# Power.net
KiCad netlist of a schematic drawn in Altium Designer
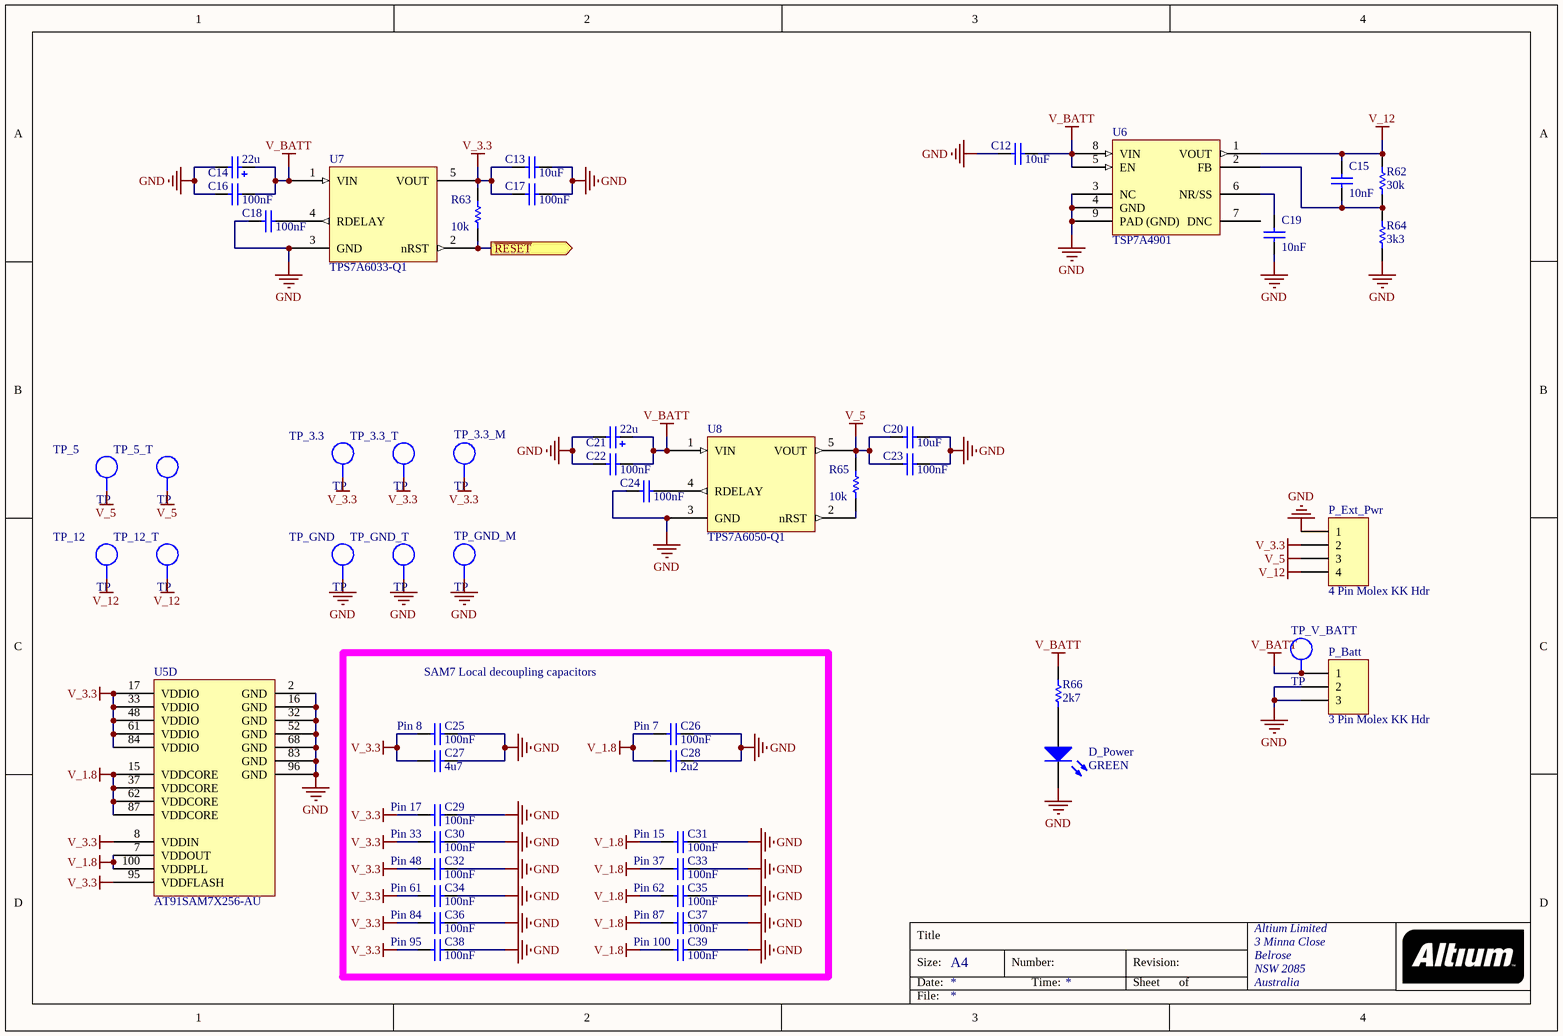
[diagram p0: Power.SchDoc]

(export (version "E")
  (design (tool "Eeschema 10.0.6"))
  (components
    (comp (ref "C12")
      (value "10uF")
      (footprint "0805")
      (description "CAP 10uF 10% 10V X5R 0805")
      (fields (field (name "MANUFACTURER") "Murata") (field (name "PART NUMBER") "CP_10uF 0805"))
      (libsource (lib "ENEL429_4") (part "CP_10uF 0805"))
    )
    (comp (ref "C13")
      (value "10uF")
      (footprint "0805")
      (description "CAP 10uF 10% 10V X5R 0805")
      (fields (field (name "PART NUMBER") "CP_10uF 0805") (field (name "MANUFACTURER") "Murata"))
      (libsource (lib "ENEL429_4") (part "CP_10uF 0805"))
    )
    (comp (ref "C14")
      (value "22u")
      (footprint "6032")
      (description "CAP TANT 22UF 35V 10% SMD")
      (fields (field (name "MANUFACTURER") "Vishay") (field (name "PART NUMBER") "CP_TANT_22uF_35V"))
      (libsource (lib "ENEL429_4") (part "CP_TANT_22uF_35V"))
    )
    (comp (ref "C15")
      (value "10nF")
      (footprint "0603")
      (description "CAP CER 10000PF 100V X7R 0603")
      (fields (field (name "MANUFACTURER") "Taiyo Yuden") (field (name "PART NUMBER") "CP_10nF 0603"))
      (libsource (lib "ENEL429_4") (part "CP_10nF 0603"))
    )
    (comp (ref "C16")
      (value "100nF")
      (footprint "0603")
      (description "CAP CER .10UF 50V X5R 0603")
      (fields (field (name "PART NUMBER") "CP_100nF 0603") (field (name "MANUFACTURER") "Taiyo Yuden"))
      (libsource (lib "ENEL429_4") (part "CP_100nF 0603"))
    )
    (comp (ref "C17")
      (value "100nF")
      (footprint "0603")
      (description "CAP CER .10UF 50V X5R 0603")
      (fields (field (name "PART NUMBER") "CP_100nF 0603") (field (name "MANUFACTURER") "Taiyo Yuden"))
      (libsource (lib "ENEL429_4") (part "CP_100nF 0603"))
    )
    (comp (ref "C18")
      (value "100nF")
      (footprint "0603")
      (description "CAP CER .10UF 50V X5R 0603")
      (fields (field (name "MANUFACTURER") "Taiyo Yuden") (field (name "PART NUMBER") "CP_100nF 0603"))
      (libsource (lib "ENEL429_4") (part "CP_100nF 0603"))
    )
    (comp (ref "C19")
      (value "10nF")
      (footprint "0603")
      (description "CAP CER 10000PF 100V X7R 0603")
      (fields (field (name "MANUFACTURER") "Taiyo Yuden") (field (name "PART NUMBER") "CP_10nF 0603"))
      (libsource (lib "ENEL429_4") (part "CP_10nF 0603"))
    )
    (comp (ref "C20")
      (value "10uF")
      (footprint "0805")
      (description "CAP 10uF 10% 10V X5R 0805")
      (fields (field (name "PART NUMBER") "CP_10uF 0805") (field (name "MANUFACTURER") "Murata"))
      (libsource (lib "ENEL429_4") (part "CP_10uF 0805"))
    )
    (comp (ref "C21")
      (value "22u")
      (footprint "6032")
      (description "CAP TANT 22UF 35V 10% SMD")
      (fields (field (name "MANUFACTURER") "Vishay") (field (name "PART NUMBER") "CP_TANT_22uF_35V"))
      (libsource (lib "ENEL429_4") (part "CP_TANT_22uF_35V"))
    )
    (comp (ref "C22")
      (value "100nF")
      (footprint "0603")
      (description "CAP CER .10UF 50V X5R 0603")
      (fields (field (name "PART NUMBER") "CP_100nF 0603") (field (name "MANUFACTURER") "Taiyo Yuden"))
      (libsource (lib "ENEL429_4") (part "CP_100nF 0603"))
    )
    (comp (ref "C23")
      (value "100nF")
      (footprint "0603")
      (description "CAP CER .10UF 50V X5R 0603")
      (fields (field (name "PART NUMBER") "CP_100nF 0603") (field (name "MANUFACTURER") "Taiyo Yuden"))
      (libsource (lib "ENEL429_4") (part "CP_100nF 0603"))
    )
    (comp (ref "C24")
      (value "100nF")
      (footprint "0603")
      (description "CAP CER .10UF 50V X5R 0603")
      (fields (field (name "MANUFACTURER") "Taiyo Yuden") (field (name "PART NUMBER") "CP_100nF 0603"))
      (libsource (lib "ENEL429_4") (part "CP_100nF 0603"))
    )
    (comp (ref "C25")
      (value "100nF")
      (footprint "0603")
      (description "CAP CER .10UF 50V X5R 0603")
      (fields (field (name "PART NUMBER") "CP_100nF 0603") (field (name "MANUFACTURER") "Taiyo Yuden"))
      (libsource (lib "ENEL429_4") (part "CP_100nF 0603"))
    )
    (comp (ref "C26")
      (value "100nF")
      (footprint "0603")
      (description "CAP CER .10UF 50V X5R 0603")
      (fields (field (name "PART NUMBER") "CP_100nF 0603") (field (name "MANUFACTURER") "Taiyo Yuden"))
      (libsource (lib "ENEL429_4") (part "CP_100nF 0603"))
    )
    (comp (ref "C27")
      (value "4u7")
      (footprint "0603")
      (description "CAP CER 4.7UF 10V X5R 0603")
      (fields
        (field (name "PART NUMBER") "CP_4u7 0603")
        (field (name "MANUFACTURER") "Taiyo Yuden LMK107BJ475KA-T")
      )
      (libsource (lib "ENEL429_4") (part "CP_4u7 0603"))
    )
    (comp (ref "C28")
      (value "2u2")
      (footprint "0603")
      (description "CAP CER 2.2UF 10V 10% X5R 0603")
      (fields
        (field (name "PART NUMBER") "CP_2u2F_10V_0603")
        (field (name "MANUFACTURER") "Murata Electronics North America")
        (field (name "VERIFY") "not verified")
      )
      (libsource (lib "ENEL429_4") (part "CP_2u2F_10V_0603"))
    )
    (comp (ref "C29")
      (value "100nF")
      (footprint "0603")
      (description "CAP CER .10UF 50V X5R 0603")
      (fields (field (name "PART NUMBER") "CP_100nF 0603") (field (name "MANUFACTURER") "Taiyo Yuden"))
      (libsource (lib "ENEL429_4") (part "CP_100nF 0603"))
    )
    (comp (ref "C30")
      (value "100nF")
      (footprint "0603")
      (description "CAP CER .10UF 50V X5R 0603")
      (fields (field (name "PART NUMBER") "CP_100nF 0603") (field (name "MANUFACTURER") "Taiyo Yuden"))
      (libsource (lib "ENEL429_4") (part "CP_100nF 0603"))
    )
    (comp (ref "C31")
      (value "100nF")
      (footprint "0603")
      (description "CAP CER .10UF 50V X5R 0603")
      (fields (field (name "PART NUMBER") "CP_100nF 0603") (field (name "MANUFACTURER") "Taiyo Yuden"))
      (libsource (lib "ENEL429_4") (part "CP_100nF 0603"))
    )
    (comp (ref "C32")
      (value "100nF")
      (footprint "0603")
      (description "CAP CER .10UF 50V X5R 0603")
      (fields (field (name "PART NUMBER") "CP_100nF 0603") (field (name "MANUFACTURER") "Taiyo Yuden"))
      (libsource (lib "ENEL429_4") (part "CP_100nF 0603"))
    )
    (comp (ref "C33")
      (value "100nF")
      (footprint "0603")
      (description "CAP CER .10UF 50V X5R 0603")
      (fields (field (name "PART NUMBER") "CP_100nF 0603") (field (name "MANUFACTURER") "Taiyo Yuden"))
      (libsource (lib "ENEL429_4") (part "CP_100nF 0603"))
    )
    (comp (ref "C34")
      (value "100nF")
      (footprint "0603")
      (description "CAP CER .10UF 50V X5R 0603")
      (fields (field (name "PART NUMBER") "CP_100nF 0603") (field (name "MANUFACTURER") "Taiyo Yuden"))
      (libsource (lib "ENEL429_4") (part "CP_100nF 0603"))
    )
    (comp (ref "C35")
      (value "100nF")
      (footprint "0603")
      (description "CAP CER .10UF 50V X5R 0603")
      (fields (field (name "PART NUMBER") "CP_100nF 0603") (field (name "MANUFACTURER") "Taiyo Yuden"))
      (libsource (lib "ENEL429_4") (part "CP_100nF 0603"))
    )
    (comp (ref "C36")
      (value "100nF")
      (footprint "0603")
      (description "CAP CER .10UF 50V X5R 0603")
      (fields (field (name "PART NUMBER") "CP_100nF 0603") (field (name "MANUFACTURER") "Taiyo Yuden"))
      (libsource (lib "ENEL429_4") (part "CP_100nF 0603"))
    )
    (comp (ref "C37")
      (value "100nF")
      (footprint "0603")
      (description "CAP CER .10UF 50V X5R 0603")
      (fields (field (name "PART NUMBER") "CP_100nF 0603") (field (name "MANUFACTURER") "Taiyo Yuden"))
      (libsource (lib "ENEL429_4") (part "CP_100nF 0603"))
    )
    (comp (ref "C38")
      (value "100nF")
      (footprint "0603")
      (description "CAP CER .10UF 50V X5R 0603")
      (fields (field (name "PART NUMBER") "CP_100nF 0603") (field (name "MANUFACTURER") "Taiyo Yuden"))
      (libsource (lib "ENEL429_4") (part "CP_100nF 0603"))
    )
    (comp (ref "C39")
      (value "100nF")
      (footprint "0603")
      (description "CAP CER .10UF 50V X5R 0603")
      (fields (field (name "PART NUMBER") "CP_100nF 0603") (field (name "MANUFACTURER") "Taiyo Yuden"))
      (libsource (lib "ENEL429_4") (part "CP_100nF 0603"))
    )
    (comp (ref "D_Power")
      (value "GREEN")
      (footprint "DIODE_0805")
      (description "Green LED 0805")
      (fields (field (name "MANUFACTURER") "Vishay") (field (name "PART NUMBER") "DL_LED Green 0805"))
      (libsource (lib "ENEL429_4") (part "DL_LED Green 0805"))
    )
    (comp (ref "P_Batt")
      (value "3 Pin Molex KK Hdr")
      (footprint "G_MOLEX_KK_3_HDR")
      (description "CONN HEADER 3POS .100 VERT TIN")
      (fields (field (name "MANUFACTURER") "Molex/Waldom") (field (name "PART NUMBER") "JP_MOLEX_KK_3POS"))
      (libsource (lib "ENEL429_4") (part "JP_MOLEX_KK_3POS"))
    )
    (comp (ref "P_Ext_Pwr")
      (value "4 Pin Molex KK Hdr")
      (footprint "G_MOLEX_KK_4_HDR")
      (description "CONN HEADER 4POS .100 VERT TIN")
      (fields (field (name "MANUFACTURER") "Molex/Waldom") (field (name "PART NUMBER") "JP_MOLEX_KK_4POS"))
      (libsource (lib "ENEL429_4") (part "JP_MOLEX_KK_4POS"))
    )
    (comp (ref "R62")
      (value "30k")
      (footprint "0603")
      (description "RES 30K OHM 1/10W 1% 0603 SMD")
      (fields (field (name "MANUFACTURER") "Yageo") (field (name "PART NUMBER") "RS_30k 0603"))
      (libsource (lib "ENEL429_4") (part "RS_30k 0603"))
    )
    (comp (ref "R63")
      (value "10k")
      (footprint "0603")
      (description "RES 10.0K OHM 1/10W 1% 0603 SMD")
      (fields (field (name "MANUFACTURER") "Yageo") (field (name "PART NUMBER") "RS_10k 0603"))
      (libsource (lib "ENEL429_4") (part "RS_10k 0603"))
    )
    (comp (ref "R64")
      (value "3k3")
      (footprint "0603")
      (description "RES 3.3K OHM 1/10W 5% 0603 SMD")
      (fields (field (name "MANUFACTURER") "Yageo") (field (name "PART NUMBER") "RS_3k3 0603"))
      (libsource (lib "ENEL429_4") (part "RS_3k3 0603"))
    )
    (comp (ref "R65")
      (value "10k")
      (footprint "0603")
      (description "RES 10.0K OHM 1/10W 1% 0603 SMD")
      (fields (field (name "MANUFACTURER") "Yageo") (field (name "PART NUMBER") "RS_10k 0603"))
      (libsource (lib "ENEL429_4") (part "RS_10k 0603"))
    )
    (comp (ref "R66")
      (value "2k7")
      (footprint "0603")
      (description "RES 2.7K OHM 1/10W 5% 0603 SMD")
      (fields (field (name "MANUFACTURER") "Yageo") (field (name "PART NUMBER") "RS_2k7 0603"))
      (libsource (lib "ENEL429_4") (part "RS_2k7 0603"))
    )
    (comp (ref "TP_3.3")
      (value "TP")
      (footprint "TEST_POINT_4X2MM")
      (description "Test-Point")
      (fields (field (name "PART NUMBER") "TP_TESTPOINT"))
      (libsource (lib "ENEL429_4") (part "TP_TESTPOINT"))
    )
    (comp (ref "TP_3.3_M")
      (value "TP")
      (footprint "TEST_POINT_4X2MM")
      (description "Test-Point")
      (fields (field (name "PART NUMBER") "TP_TESTPOINT"))
      (libsource (lib "ENEL429_4") (part "TP_TESTPOINT"))
    )
    (comp (ref "TP_3.3_T")
      (value "TP")
      (footprint "TEST_POINT_4X2MM")
      (description "Test-Point")
      (fields (field (name "PART NUMBER") "TP_TESTPOINT"))
      (libsource (lib "ENEL429_4") (part "TP_TESTPOINT"))
    )
    (comp (ref "TP_5")
      (value "TP")
      (footprint "TEST_POINT_4X2MM")
      (description "Test-Point")
      (fields (field (name "PART NUMBER") "TP_TESTPOINT"))
      (libsource (lib "ENEL429_4") (part "TP_TESTPOINT"))
    )
    (comp (ref "TP_5_T")
      (value "TP")
      (footprint "TEST_POINT_4X2MM")
      (description "Test-Point")
      (fields (field (name "PART NUMBER") "TP_TESTPOINT"))
      (libsource (lib "ENEL429_4") (part "TP_TESTPOINT"))
    )
    (comp (ref "TP_12")
      (value "TP")
      (footprint "TEST_POINT_4X2MM")
      (description "Test-Point")
      (fields (field (name "PART NUMBER") "TP_TESTPOINT"))
      (libsource (lib "ENEL429_4") (part "TP_TESTPOINT"))
    )
    (comp (ref "TP_12_T")
      (value "TP")
      (footprint "TEST_POINT_4X2MM")
      (description "Test-Point")
      (fields (field (name "PART NUMBER") "TP_TESTPOINT"))
      (libsource (lib "ENEL429_4") (part "TP_TESTPOINT"))
    )
    (comp (ref "TP_GND")
      (value "TP")
      (footprint "TEST_POINT_4X2MM")
      (description "Test-Point")
      (fields (field (name "PART NUMBER") "TP_TESTPOINT"))
      (libsource (lib "ENEL429_4") (part "TP_TESTPOINT"))
    )
    (comp (ref "TP_GND_M")
      (value "TP")
      (footprint "TEST_POINT_4X2MM")
      (description "Test-Point")
      (fields (field (name "PART NUMBER") "TP_TESTPOINT"))
      (libsource (lib "ENEL429_4") (part "TP_TESTPOINT"))
    )
    (comp (ref "TP_GND_T")
      (value "TP")
      (footprint "TEST_POINT_4X2MM")
      (description "Test-Point")
      (fields (field (name "PART NUMBER") "TP_TESTPOINT"))
      (libsource (lib "ENEL429_4") (part "TP_TESTPOINT"))
    )
    (comp (ref "TP_V_BATT")
      (value "TP")
      (footprint "TEST_POINT_4X2MM")
      (description "Test-Point")
      (fields (field (name "PART NUMBER") "TP_TESTPOINT"))
      (libsource (lib "ENEL429_4") (part "TP_TESTPOINT"))
    )
    (comp (ref "U5")
      (value "AT91SAM7X256-AU")
      (footprint "LQFP100_N")
      (fields (field (name "PUBLISHER") "Altium Limited"))
      (libsource (lib "Atmel Microcontroller 32-Bit ARM") (part "AT91SAM7X256-AU"))
    )
    (comp (ref "U6")
      (value "TSP7A4901")
      (footprint "TSOP65P490X110_HS-8N")
      (libsource (lib "MarioLib") (part "TSP7A4901"))
    )
    (comp (ref "U7")
      (value "TPS7A6033-Q1")
      (footprint "TO170P1524X483-6N")
      (libsource (lib "MarioLib") (part "TPS7A6033-Q1"))
    )
    (comp (ref "U8")
      (value "TPS7A6050-Q1")
      (footprint "TO170P1524X483-6N")
      (libsource (lib "MarioLib") (part "TPS7A6050-Q1"))
    )
  )
  (nets
    (net (code "1") (name "/~{RESET}") (class "Default")
      (node (ref "R63") (pin "1") (pinfunction "1_1") (pintype "passive"))
      (node (ref "U7") (pin "2") (pinfunction "nRST_2") (pintype "output"))
    )
    (net (code "2") (name "GND") (class "Default")
      (node (ref "C12") (pin "1") (pinfunction "1_1") (pintype "passive"))
      (node (ref "C13") (pin "2") (pinfunction "2_2") (pintype "passive"))
      (node (ref "C14") (pin "2") (pinfunction "2_2") (pintype "passive"))
      (node (ref "C16") (pin "1") (pinfunction "1_1") (pintype "passive"))
      (node (ref "C17") (pin "1") (pinfunction "1_1") (pintype "passive"))
      (node (ref "C18") (pin "1") (pinfunction "1_1") (pintype "passive"))
      (node (ref "C19") (pin "1") (pinfunction "1_1") (pintype "passive"))
      (node (ref "C20") (pin "2") (pinfunction "2_2") (pintype "passive"))
      (node (ref "C21") (pin "2") (pinfunction "2_2") (pintype "passive"))
      (node (ref "C22") (pin "1") (pinfunction "1_1") (pintype "passive"))
      (node (ref "C23") (pin "1") (pinfunction "1_1") (pintype "passive"))
      (node (ref "C24") (pin "1") (pinfunction "1_1") (pintype "passive"))
      (node (ref "C25") (pin "2") (pinfunction "2_2") (pintype "passive"))
      (node (ref "C26") (pin "2") (pinfunction "2_2") (pintype "passive"))
      (node (ref "C27") (pin "2") (pinfunction "2_2") (pintype "passive"))
      (node (ref "C28") (pin "2") (pinfunction "2_2") (pintype "passive"))
      (node (ref "C29") (pin "2") (pinfunction "2_2") (pintype "passive"))
      (node (ref "C30") (pin "2") (pinfunction "2_2") (pintype "passive"))
      (node (ref "C31") (pin "2") (pinfunction "2_2") (pintype "passive"))
      (node (ref "C32") (pin "2") (pinfunction "2_2") (pintype "passive"))
      (node (ref "C33") (pin "2") (pinfunction "2_2") (pintype "passive"))
      (node (ref "C34") (pin "2") (pinfunction "2_2") (pintype "passive"))
      (node (ref "C35") (pin "2") (pinfunction "2_2") (pintype "passive"))
      (node (ref "C36") (pin "2") (pinfunction "2_2") (pintype "passive"))
      (node (ref "C37") (pin "2") (pinfunction "2_2") (pintype "passive"))
      (node (ref "C38") (pin "2") (pinfunction "2_2") (pintype "passive"))
      (node (ref "C39") (pin "2") (pinfunction "2_2") (pintype "passive"))
      (node (ref "D_Power") (pin "2") (pinfunction "K_2") (pintype "passive"))
      (node (ref "P_Batt") (pin "2") (pinfunction "2_2") (pintype "passive"))
      (node (ref "P_Batt") (pin "3") (pinfunction "3_3") (pintype "passive"))
      (node (ref "P_Ext_Pwr") (pin "1") (pinfunction "1_1") (pintype "passive"))
      (node (ref "R64") (pin "1") (pinfunction "1_1") (pintype "passive"))
      (node (ref "TP_GND") (pin "1") (pinfunction "1_1") (pintype "passive"))
      (node (ref "TP_GND_M") (pin "1") (pinfunction "1_1") (pintype "passive"))
      (node (ref "TP_GND_T") (pin "1") (pinfunction "1_1") (pintype "passive"))
      (node (ref "U5") (pin "16") (pinfunction "GND_16") (pintype "power_in"))
      (node (ref "U5") (pin "2") (pinfunction "GND_2") (pintype "power_in"))
      (node (ref "U5") (pin "32") (pinfunction "GND_32") (pintype "power_in"))
      (node (ref "U5") (pin "52") (pinfunction "GND_52") (pintype "power_in"))
      (node (ref "U5") (pin "68") (pinfunction "GND_68") (pintype "power_in"))
      (node (ref "U5") (pin "83") (pinfunction "GND_83") (pintype "power_in"))
      (node (ref "U5") (pin "96") (pinfunction "GND_96") (pintype "power_in"))
      (node (ref "U6") (pin "3") (pinfunction "NC_3") (pintype "passive"))
      (node (ref "U6") (pin "4") (pinfunction "GND_4") (pintype "passive"))
      (node (ref "U6") (pin "9") (pinfunction "PAD_(GND)_9") (pintype "passive"))
      (node (ref "U7") (pin "3") (pinfunction "GND_3") (pintype "passive"))
      (node (ref "U8") (pin "3") (pinfunction "GND_3") (pintype "passive"))
    )
    (net (code "3") (name "Net-(D_Power-A)") (class "Default")
      (node (ref "D_Power") (pin "1") (pinfunction "A_1") (pintype "passive"))
      (node (ref "R66") (pin "1") (pinfunction "1_1") (pintype "passive"))
    )
    (net (code "4") (name "Net-(U6-FB)") (class "Default")
      (node (ref "C15") (pin "1") (pinfunction "1_1") (pintype "passive"))
      (node (ref "R62") (pin "1") (pinfunction "1_1") (pintype "passive"))
      (node (ref "R64") (pin "2") (pinfunction "2_2") (pintype "passive"))
      (node (ref "U6") (pin "2") (pinfunction "FB_2") (pintype "passive"))
    )
    (net (code "5") (name "Net-(U6-NR{slash}SS)") (class "Default")
      (node (ref "C19") (pin "2") (pinfunction "2_2") (pintype "passive"))
      (node (ref "U6") (pin "6") (pinfunction "NR/SS_6") (pintype "passive"))
    )
    (net (code "6") (name "Net-(U7-RDELAY)") (class "Default")
      (node (ref "C18") (pin "2") (pinfunction "2_2") (pintype "passive"))
      (node (ref "U7") (pin "4") (pinfunction "RDELAY_4") (pintype "output"))
    )
    (net (code "7") (name "Net-(U8-RDELAY)") (class "Default")
      (node (ref "C24") (pin "2") (pinfunction "2_2") (pintype "passive"))
      (node (ref "U8") (pin "4") (pinfunction "RDELAY_4") (pintype "output"))
    )
    (net (code "8") (name "Net-(U8-nRST)") (class "Default")
      (node (ref "R65") (pin "1") (pinfunction "1_1") (pintype "passive"))
      (node (ref "U8") (pin "2") (pinfunction "nRST_2") (pintype "output"))
    )
    (net (code "9") (name "V_1.8") (class "Default")
      (node (ref "C26") (pin "1") (pinfunction "1_1") (pintype "passive"))
      (node (ref "C28") (pin "1") (pinfunction "1_1") (pintype "passive"))
      (node (ref "C31") (pin "1") (pinfunction "1_1") (pintype "passive"))
      (node (ref "C33") (pin "1") (pinfunction "1_1") (pintype "passive"))
      (node (ref "C35") (pin "1") (pinfunction "1_1") (pintype "passive"))
      (node (ref "C37") (pin "1") (pinfunction "1_1") (pintype "passive"))
      (node (ref "C39") (pin "1") (pinfunction "1_1") (pintype "passive"))
      (node (ref "U5") (pin "100") (pinfunction "VDDPLL_100") (pintype "power_in"))
      (node (ref "U5") (pin "15") (pinfunction "VDDCORE_15") (pintype "power_in"))
      (node (ref "U5") (pin "37") (pinfunction "VDDCORE_37") (pintype "power_in"))
      (node (ref "U5") (pin "62") (pinfunction "VDDCORE_62") (pintype "power_in"))
      (node (ref "U5") (pin "7") (pinfunction "VDDOUT_7") (pintype "power_in"))
      (node (ref "U5") (pin "87") (pinfunction "VDDCORE_87") (pintype "power_in"))
    )
    (net (code "10") (name "V_3.3") (class "Default")
      (node (ref "C13") (pin "1") (pinfunction "1_1") (pintype "passive"))
      (node (ref "C17") (pin "2") (pinfunction "2_2") (pintype "passive"))
      (node (ref "C25") (pin "1") (pinfunction "1_1") (pintype "passive"))
      (node (ref "C27") (pin "1") (pinfunction "1_1") (pintype "passive"))
      (node (ref "C29") (pin "1") (pinfunction "1_1") (pintype "passive"))
      (node (ref "C30") (pin "1") (pinfunction "1_1") (pintype "passive"))
      (node (ref "C32") (pin "1") (pinfunction "1_1") (pintype "passive"))
      (node (ref "C34") (pin "1") (pinfunction "1_1") (pintype "passive"))
      (node (ref "C36") (pin "1") (pinfunction "1_1") (pintype "passive"))
      (node (ref "C38") (pin "1") (pinfunction "1_1") (pintype "passive"))
      (node (ref "P_Ext_Pwr") (pin "2") (pinfunction "2_2") (pintype "passive"))
      (node (ref "R63") (pin "2") (pinfunction "2_2") (pintype "passive"))
      (node (ref "TP_3.3") (pin "1") (pinfunction "1_1") (pintype "passive"))
      (node (ref "TP_3.3_M") (pin "1") (pinfunction "1_1") (pintype "passive"))
      (node (ref "TP_3.3_T") (pin "1") (pinfunction "1_1") (pintype "passive"))
      (node (ref "U5") (pin "17") (pinfunction "VDDIO_17") (pintype "power_in"))
      (node (ref "U5") (pin "33") (pinfunction "VDDIO_33") (pintype "power_in"))
      (node (ref "U5") (pin "48") (pinfunction "VDDIO_48") (pintype "power_in"))
      (node (ref "U5") (pin "61") (pinfunction "VDDIO_61") (pintype "power_in"))
      (node (ref "U5") (pin "8") (pinfunction "VDDIN_8") (pintype "power_in"))
      (node (ref "U5") (pin "84") (pinfunction "VDDIO_84") (pintype "power_in"))
      (node (ref "U5") (pin "95") (pinfunction "VDDFLASH_95") (pintype "power_in"))
      (node (ref "U7") (pin "5") (pinfunction "VOUT_5") (pintype "power_in"))
    )
    (net (code "11") (name "V_5") (class "Default")
      (node (ref "C20") (pin "1") (pinfunction "1_1") (pintype "passive"))
      (node (ref "C23") (pin "2") (pinfunction "2_2") (pintype "passive"))
      (node (ref "P_Ext_Pwr") (pin "3") (pinfunction "3_3") (pintype "passive"))
      (node (ref "R65") (pin "2") (pinfunction "2_2") (pintype "passive"))
      (node (ref "TP_5") (pin "1") (pinfunction "1_1") (pintype "passive"))
      (node (ref "TP_5_T") (pin "1") (pinfunction "1_1") (pintype "passive"))
      (node (ref "U8") (pin "5") (pinfunction "VOUT_5") (pintype "output"))
    )
    (net (code "12") (name "V_12") (class "Default")
      (node (ref "C15") (pin "2") (pinfunction "2_2") (pintype "passive"))
      (node (ref "P_Ext_Pwr") (pin "4") (pinfunction "4_4") (pintype "passive"))
      (node (ref "R62") (pin "2") (pinfunction "2_2") (pintype "passive"))
      (node (ref "TP_12") (pin "1") (pinfunction "1_1") (pintype "passive"))
      (node (ref "TP_12_T") (pin "1") (pinfunction "1_1") (pintype "passive"))
      (node (ref "U6") (pin "1") (pinfunction "VOUT_1") (pintype "output"))
    )
    (net (code "13") (name "V_BATT") (class "Default")
      (node (ref "C12") (pin "2") (pinfunction "2_2") (pintype "passive"))
      (node (ref "C14") (pin "1") (pinfunction "1_1") (pintype "passive"))
      (node (ref "C16") (pin "2") (pinfunction "2_2") (pintype "passive"))
      (node (ref "C21") (pin "1") (pinfunction "1_1") (pintype "passive"))
      (node (ref "C22") (pin "2") (pinfunction "2_2") (pintype "passive"))
      (node (ref "P_Batt") (pin "1") (pinfunction "1_1") (pintype "passive"))
      (node (ref "R66") (pin "2") (pinfunction "2_2") (pintype "passive"))
      (node (ref "TP_V_BATT") (pin "1") (pinfunction "1_1") (pintype "passive"))
      (node (ref "U6") (pin "5") (pinfunction "EN_5") (pintype "input"))
      (node (ref "U6") (pin "8") (pinfunction "VIN_8") (pintype "input"))
      (node (ref "U7") (pin "1") (pinfunction "VIN_1") (pintype "input"))
      (node (ref "U8") (pin "1") (pinfunction "VIN_1") (pintype "input"))
    )
    (net (code "14") (name "unconnected-(U6-DNC-Pad7)") (class "Default")
      (node (ref "U6") (pin "7") (pinfunction "DNC_7") (pintype "passive"))
    )
  )
)
